# MAGI_sM0Core.net
KiCad netlist of a schematic drawn in Altium Designer
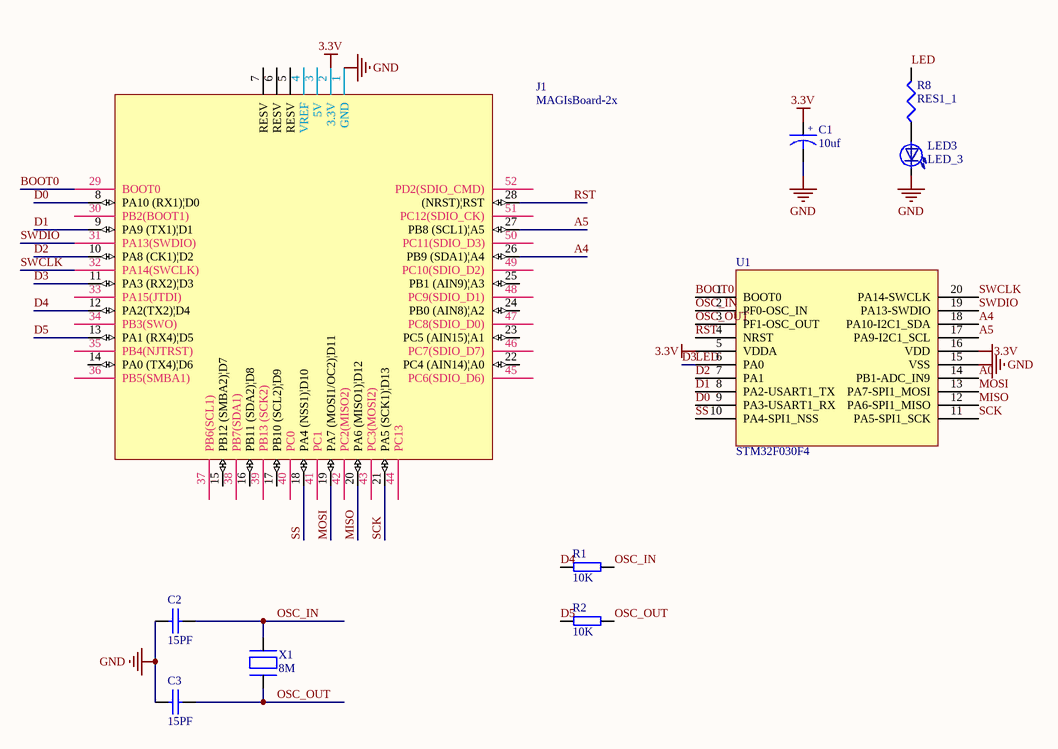
[diagram p0: MAGI'sM0Core.SchDoc]

(export (version "E")
  (design (tool "Eeschema 10.0.6"))
  (components
    (comp (ref "C1")
      (value "10uf")
      (footprint "6-0805_n")
      (description "Capacitor")
      (libsource (lib "电容器") (part "CAPACITOR POL"))
    )
    (comp (ref "C2") (value "15PF") (footprint "6-0805_n") (libsource (lib "STM32") (part "CAP")))
    (comp (ref "C3") (value "15PF") (footprint "6-0805_n") (libsource (lib "STM32") (part "CAP")))
    (comp (ref "J1")
      (value "MAGIsBoard-2x")
      (footprint "MAGIsBoard-2x")
      (libsource (lib "MAGIsBoard") (part "MAGIsBoard-2x"))
    )
    (comp (ref "LED3") (value "LED_3") (footprint "6-0805_N") (libsource (lib "二极管") (part "LED_3")))
    (comp (ref "R1") (value "10K") (footprint "6-0805_n") (libsource (lib "STM32") (part "RES")))
    (comp (ref "R2") (value "10K") (footprint "6-0805_n") (libsource (lib "STM32") (part "RES")))
    (comp (ref "R8") (value "RES1_1") (footprint "6-0805_N") (libsource (lib "电阻器") (part "RES1_1")))
    (comp (ref "U1")
      (value "STM32F030F4")
      (footprint "STM32F030")
      (libsource (lib "MCU") (part "STM32F030F4"))
    )
    (comp (ref "X1") (value "8M") (footprint "5032") (libsource (lib "STM32") (part "CRYSTAL")))
  )
  (nets
    (net (code "1") (name "/A0") (class "Default")
      (node (ref "U1") (pin "14") (pinfunction "PB1-ADC_IN9_14") (pintype "passive"))
    )
    (net (code "2") (name "/A4") (class "Default")
      (node (ref "J1") (pin "26") (pinfunction "PB9_(SDA1)¦A4_26") (pintype "bidirectional"))
      (node (ref "U1") (pin "18") (pinfunction "PA10-I2C1_SDA_18") (pintype "passive"))
    )
    (net (code "3") (name "/A5") (class "Default")
      (node (ref "J1") (pin "27") (pinfunction "PB8_(SCL1)¦A5_27") (pintype "bidirectional"))
      (node (ref "U1") (pin "17") (pinfunction "PA9-I2C1_SCL_17") (pintype "passive"))
    )
    (net (code "4") (name "/BOOT0") (class "Default")
      (node (ref "J1") (pin "29") (pinfunction "BOOT0_29") (pintype "passive"))
      (node (ref "U1") (pin "1") (pinfunction "BOOT0_1") (pintype "passive"))
    )
    (net (code "5") (name "/D0") (class "Default")
      (node (ref "J1") (pin "8") (pinfunction "PA10_(RX1)¦D0_8") (pintype "bidirectional"))
      (node (ref "U1") (pin "9") (pinfunction "PA3-USART1_RX_9") (pintype "passive"))
    )
    (net (code "6") (name "/D1") (class "Default")
      (node (ref "J1") (pin "9") (pinfunction "PA9_(TX1)¦D1_9") (pintype "bidirectional"))
      (node (ref "U1") (pin "8") (pinfunction "PA2-USART1_TX_8") (pintype "passive"))
    )
    (net (code "7") (name "/D2") (class "Default")
      (node (ref "J1") (pin "10") (pinfunction "PA8_(CK1)¦D2_10") (pintype "bidirectional"))
      (node (ref "U1") (pin "7") (pinfunction "PA1_7") (pintype "passive"))
    )
    (net (code "8") (name "/D3") (class "Default")
      (node (ref "J1") (pin "11") (pinfunction "PA3_(RX2)¦D3_11") (pintype "bidirectional"))
      (node (ref "R8") (pin "2") (pinfunction "2_2") (pintype "passive"))
      (node (ref "U1") (pin "6") (pinfunction "PA0_6") (pintype "passive"))
    )
    (net (code "9") (name "/D4") (class "Default")
      (node (ref "J1") (pin "12") (pinfunction "PA2(TX2)¦D4_12") (pintype "bidirectional"))
      (node (ref "R1") (pin "2") (pinfunction "2_2") (pintype "passive"))
    )
    (net (code "10") (name "/D5") (class "Default")
      (node (ref "J1") (pin "13") (pinfunction "PA1_(RX4)¦D5_13") (pintype "bidirectional"))
      (node (ref "R2") (pin "2") (pinfunction "2_2") (pintype "passive"))
    )
    (net (code "11") (name "/MISO") (class "Default")
      (node (ref "J1") (pin "20") (pinfunction "PA6_(MISO1)¦D12_20") (pintype "bidirectional"))
      (node (ref "U1") (pin "12") (pinfunction "PA6-SPI1_MISO_12") (pintype "passive"))
    )
    (net (code "12") (name "/MOSI") (class "Default")
      (node (ref "J1") (pin "19") (pinfunction "PA7_(MOSI1/OC2)¦D11_19") (pintype "bidirectional"))
      (node (ref "U1") (pin "13") (pinfunction "PA7-SPI1_MOSI_13") (pintype "passive"))
    )
    (net (code "13") (name "/OSC_IN") (class "Default")
      (node (ref "C2") (pin "2") (pinfunction "2_2") (pintype "passive"))
      (node (ref "R1") (pin "1") (pinfunction "1_1") (pintype "passive"))
      (node (ref "U1") (pin "2") (pinfunction "PF0-OSC_IN_2") (pintype "passive"))
      (node (ref "X1") (pin "1") (pinfunction "1_1") (pintype "passive"))
    )
    (net (code "14") (name "/OSC_OUT") (class "Default")
      (node (ref "C3") (pin "2") (pinfunction "2_2") (pintype "passive"))
      (node (ref "R2") (pin "1") (pinfunction "1_1") (pintype "passive"))
      (node (ref "U1") (pin "3") (pinfunction "PF1-OSC_OUT_3") (pintype "passive"))
      (node (ref "X1") (pin "2") (pinfunction "2_2") (pintype "passive"))
    )
    (net (code "15") (name "/RST") (class "Default")
      (node (ref "J1") (pin "28") (pinfunction "(NRST)¦RST_28") (pintype "bidirectional"))
      (node (ref "U1") (pin "4") (pinfunction "NRST_4") (pintype "passive"))
    )
    (net (code "16") (name "/SCK") (class "Default")
      (node (ref "J1") (pin "21") (pinfunction "PA5_(SCK1)¦D13_21") (pintype "bidirectional"))
      (node (ref "U1") (pin "11") (pinfunction "PA5-SPI1_SCK_11") (pintype "passive"))
    )
    (net (code "17") (name "/SS") (class "Default")
      (node (ref "J1") (pin "18") (pinfunction "PA4_(NSS1)¦D10_18") (pintype "bidirectional"))
      (node (ref "U1") (pin "10") (pinfunction "PA4-SPI1_NSS_10") (pintype "passive"))
    )
    (net (code "18") (name "/SWCLK") (class "Default")
      (node (ref "J1") (pin "32") (pinfunction "PA14(SWCLK)_32") (pintype "passive"))
      (node (ref "U1") (pin "20") (pinfunction "PA14-SWCLK_20") (pintype "passive"))
    )
    (net (code "19") (name "/SWDIO") (class "Default")
      (node (ref "J1") (pin "31") (pinfunction "PA13(SWDIO)_31") (pintype "passive"))
      (node (ref "U1") (pin "19") (pinfunction "PA13-SWDIO_19") (pintype "passive"))
    )
    (net (code "20") (name "3.3V") (class "Default")
      (node (ref "C1") (pin "1") (pinfunction "1_1") (pintype "passive"))
      (node (ref "J1") (pin "2") (pinfunction "3.3V_2") (pintype "power_in"))
      (node (ref "U1") (pin "16") (pinfunction "VDD_16") (pintype "passive"))
      (node (ref "U1") (pin "5") (pinfunction "VDDA_5") (pintype "passive"))
    )
    (net (code "21") (name "GND") (class "Default")
      (node (ref "C1") (pin "2") (pinfunction "2_2") (pintype "passive"))
      (node (ref "C2") (pin "1") (pinfunction "1_1") (pintype "passive"))
      (node (ref "C3") (pin "1") (pinfunction "1_1") (pintype "passive"))
      (node (ref "J1") (pin "1") (pinfunction "GND_1") (pintype "power_in"))
      (node (ref "LED3") (pin "2") (pinfunction "K_2") (pintype "passive"))
      (node (ref "U1") (pin "15") (pinfunction "VSS_15") (pintype "passive"))
    )
    (net (code "22") (name "Net-(LED3-A)") (class "Default")
      (node (ref "LED3") (pin "1") (pinfunction "A_1") (pintype "passive"))
      (node (ref "R8") (pin "1") (pinfunction "1_1") (pintype "passive"))
    )
    (net (code "23") (name "unconnected-(J1-5V-Pad3)") (class "Default")
      (node (ref "J1") (pin "3") (pinfunction "5V_3") (pintype "power_in"))
    )
    (net (code "24") (name "unconnected-(J1-PA0_(TX4)¦D6-Pad14)") (class "Default")
      (node (ref "J1") (pin "14") (pinfunction "PA0_(TX4)¦D6_14") (pintype "bidirectional"))
    )
    (net (code "25") (name "unconnected-(J1-PA15(JTDI)-Pad33)") (class "Default")
      (node (ref "J1") (pin "33") (pinfunction "PA15(JTDI)_33") (pintype "passive"))
    )
    (net (code "26") (name "unconnected-(J1-PB0_(AIN8)¦A2-Pad24)") (class "Default")
      (node (ref "J1") (pin "24") (pinfunction "PB0_(AIN8)¦A2_24") (pintype "bidirectional"))
    )
    (net (code "27") (name "unconnected-(J1-PB1_(AIN9)¦A3-Pad25)") (class "Default")
      (node (ref "J1") (pin "25") (pinfunction "PB1_(AIN9)¦A3_25") (pintype "bidirectional"))
    )
    (net (code "28") (name "unconnected-(J1-PB2(BOOT1)-Pad30)") (class "Default")
      (node (ref "J1") (pin "30") (pinfunction "PB2(BOOT1)_30") (pintype "passive"))
    )
    (net (code "29") (name "unconnected-(J1-PB3(SWO)-Pad34)") (class "Default")
      (node (ref "J1") (pin "34") (pinfunction "PB3(SWO)_34") (pintype "passive"))
    )
    (net (code "30") (name "unconnected-(J1-PB4(NJTRST)-Pad35)") (class "Default")
      (node (ref "J1") (pin "35") (pinfunction "PB4(NJTRST)_35") (pintype "passive"))
    )
    (net (code "31") (name "unconnected-(J1-PB5(SMBA1)-Pad36)") (class "Default")
      (node (ref "J1") (pin "36") (pinfunction "PB5(SMBA1)_36") (pintype "passive"))
    )
    (net (code "32") (name "unconnected-(J1-PB6(SCL1)-Pad37)") (class "Default")
      (node (ref "J1") (pin "37") (pinfunction "PB6(SCL1)_37") (pintype "passive"))
    )
    (net (code "33") (name "unconnected-(J1-PB7(SDA1)-Pad38)") (class "Default")
      (node (ref "J1") (pin "38") (pinfunction "PB7(SDA1)_38") (pintype "passive"))
    )
    (net (code "34") (name "unconnected-(J1-PB10_(SCL2)¦D9-Pad17)") (class "Default")
      (node (ref "J1") (pin "17") (pinfunction "PB10_(SCL2)¦D9_17") (pintype "bidirectional"))
    )
    (net (code "35") (name "unconnected-(J1-PB11_(SDA2)¦D8-Pad16)") (class "Default")
      (node (ref "J1") (pin "16") (pinfunction "PB11_(SDA2)¦D8_16") (pintype "bidirectional"))
    )
    (net (code "36") (name "unconnected-(J1-PB12_(SMBA2)¦D7-Pad15)") (class "Default")
      (node (ref "J1") (pin "15") (pinfunction "PB12_(SMBA2)¦D7_15") (pintype "bidirectional"))
    )
    (net (code "37") (name "unconnected-(J1-PB13_(SCK2)-Pad39)") (class "Default")
      (node (ref "J1") (pin "39") (pinfunction "PB13_(SCK2)_39") (pintype "passive"))
    )
    (net (code "38") (name "unconnected-(J1-PC0-Pad40)") (class "Default")
      (node (ref "J1") (pin "40") (pinfunction "PC0_40") (pintype "passive"))
    )
    (net (code "39") (name "unconnected-(J1-PC1-Pad41)") (class "Default")
      (node (ref "J1") (pin "41") (pinfunction "PC1_41") (pintype "passive"))
    )
    (net (code "40") (name "unconnected-(J1-PC2(MISO2)-Pad42)") (class "Default")
      (node (ref "J1") (pin "42") (pinfunction "PC2(MISO2)_42") (pintype "passive"))
    )
    (net (code "41") (name "unconnected-(J1-PC3(MOSI2)-Pad43)") (class "Default")
      (node (ref "J1") (pin "43") (pinfunction "PC3(MOSI2)_43") (pintype "passive"))
    )
    (net (code "42") (name "unconnected-(J1-PC4_(AIN14)¦A0-Pad22)") (class "Default")
      (node (ref "J1") (pin "22") (pinfunction "PC4_(AIN14)¦A0_22") (pintype "bidirectional"))
    )
    (net (code "43") (name "unconnected-(J1-PC5_(AIN15)¦A1-Pad23)") (class "Default")
      (node (ref "J1") (pin "23") (pinfunction "PC5_(AIN15)¦A1_23") (pintype "bidirectional"))
    )
    (net (code "44") (name "unconnected-(J1-PC6(SDIO_D6)-Pad45)") (class "Default")
      (node (ref "J1") (pin "45") (pinfunction "PC6(SDIO_D6)_45") (pintype "passive"))
    )
    (net (code "45") (name "unconnected-(J1-PC7(SDIO_D7)-Pad46)") (class "Default")
      (node (ref "J1") (pin "46") (pinfunction "PC7(SDIO_D7)_46") (pintype "passive"))
    )
    (net (code "46") (name "unconnected-(J1-PC8(SDIO_D0)-Pad47)") (class "Default")
      (node (ref "J1") (pin "47") (pinfunction "PC8(SDIO_D0)_47") (pintype "passive"))
    )
    (net (code "47") (name "unconnected-(J1-PC9(SDIO_D1)-Pad48)") (class "Default")
      (node (ref "J1") (pin "48") (pinfunction "PC9(SDIO_D1)_48") (pintype "passive"))
    )
    (net (code "48") (name "unconnected-(J1-PC10(SDIO_D2)-Pad49)") (class "Default")
      (node (ref "J1") (pin "49") (pinfunction "PC10(SDIO_D2)_49") (pintype "passive"))
    )
    (net (code "49") (name "unconnected-(J1-PC11(SDIO_D3)-Pad50)") (class "Default")
      (node (ref "J1") (pin "50") (pinfunction "PC11(SDIO_D3)_50") (pintype "passive"))
    )
    (net (code "50") (name "unconnected-(J1-PC12(SDIO_CK)-Pad51)") (class "Default")
      (node (ref "J1") (pin "51") (pinfunction "PC12(SDIO_CK)_51") (pintype "passive"))
    )
    (net (code "51") (name "unconnected-(J1-PC13-Pad44)") (class "Default")
      (node (ref "J1") (pin "44") (pinfunction "PC13_44") (pintype "passive"))
    )
    (net (code "52") (name "unconnected-(J1-PD2(SDIO_CMD)-Pad52)") (class "Default")
      (node (ref "J1") (pin "52") (pinfunction "PD2(SDIO_CMD)_52") (pintype "passive"))
    )
    (net (code "53") (name "unconnected-(J1-RESV-Pad5)") (class "Default")
      (node (ref "J1") (pin "5") (pinfunction "RESV_5") (pintype "passive"))
    )
    (net (code "54") (name "unconnected-(J1-RESV-Pad6)") (class "Default")
      (node (ref "J1") (pin "6") (pinfunction "RESV_6") (pintype "passive"))
    )
    (net (code "55") (name "unconnected-(J1-RESV-Pad7)") (class "Default")
      (node (ref "J1") (pin "7") (pinfunction "RESV_7") (pintype "passive"))
    )
    (net (code "56") (name "unconnected-(J1-VREF-Pad4)") (class "Default")
      (node (ref "J1") (pin "4") (pinfunction "VREF_4") (pintype "passive"))
    )
  )
)
